# leg_module.net
KiCad netlist of a schematic drawn in Altium Designer
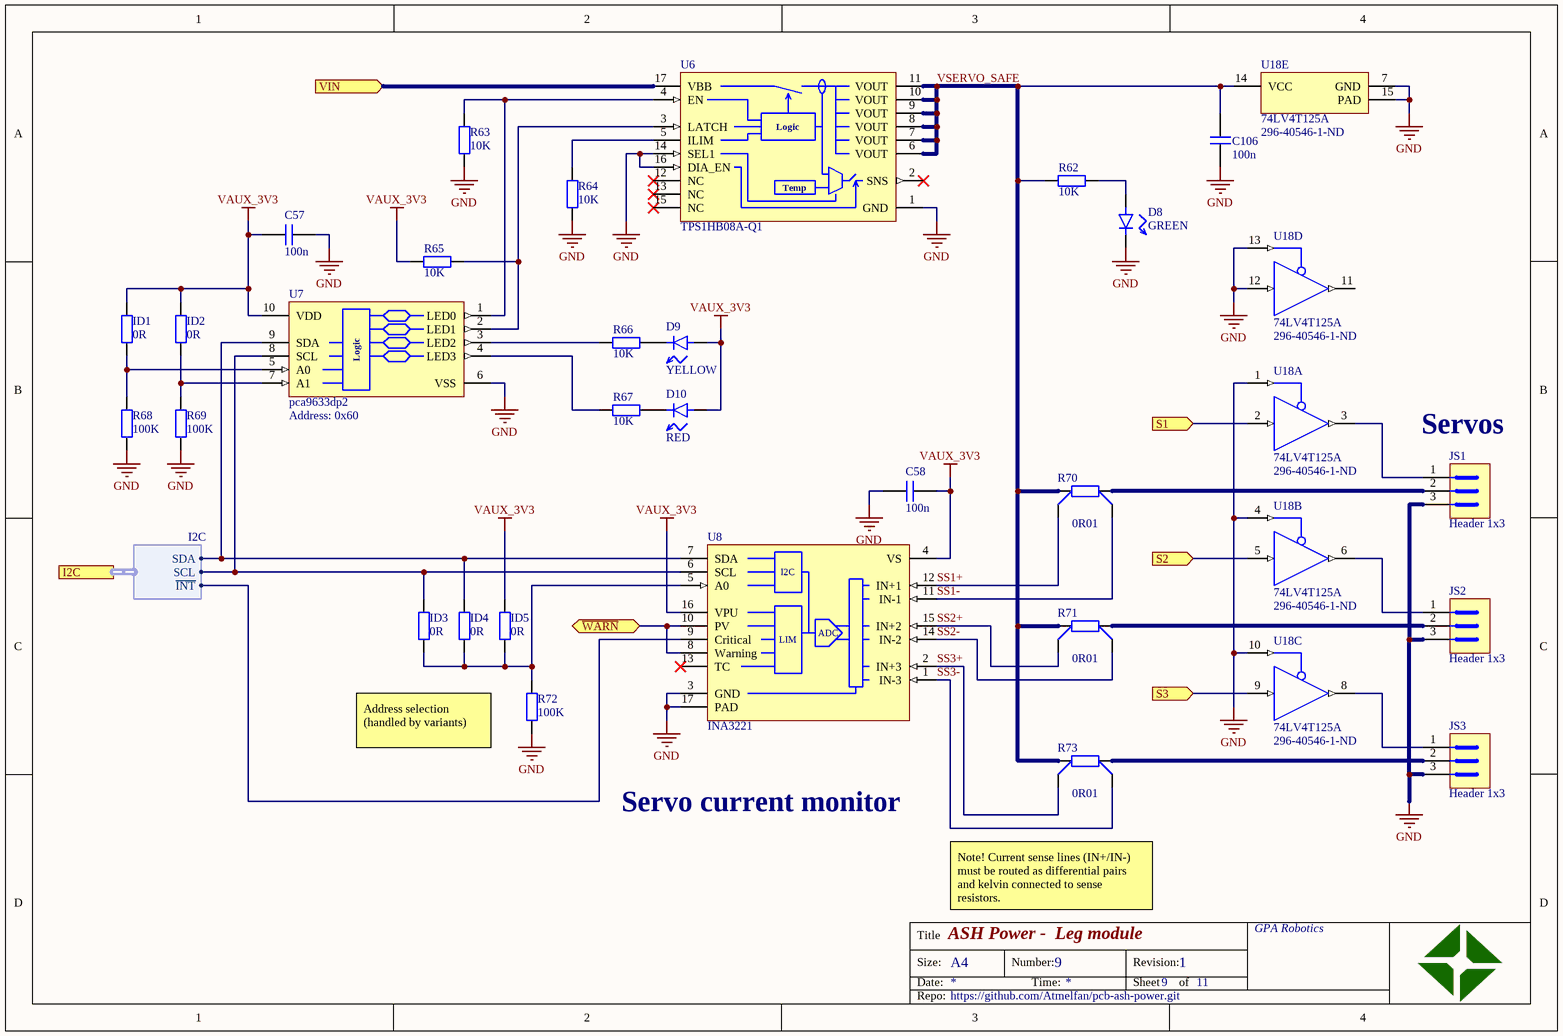
[diagram p0: leg_module.SchDoc]

(export (version "E")
  (design (tool "Eeschema 10.0.6"))
  (components
    (comp (ref "C57")
      (value "100n")
      (footprint "CAPC1005X06N")
      (description "Capacitor")
      (fields (field (name "Comment") "cap"))
      (libsource (lib "lib_passives") (part "cap"))
    )
    (comp (ref "C58")
      (value "100n")
      (footprint "CAPC1005X06N")
      (description "Capacitor")
      (fields (field (name "Comment") "cap"))
      (libsource (lib "lib_passives") (part "cap"))
    )
    (comp (ref "C106")
      (value "100n")
      (footprint "CAPC1005X06N")
      (description "Capacitor")
      (fields (field (name "Comment") "cap"))
      (libsource (lib "lib_passives") (part "cap"))
    )
    (comp (ref "D8")
      (value "GREEN")
      (footprint "CAPCP1005X06N")
      (description "LED")
      (fields (field (name "Comment") "led"))
      (libsource (lib "lib_actives") (part "led"))
    )
    (comp (ref "D9")
      (value "YELLOW")
      (footprint "CAPCP1005X06N")
      (description "LED")
      (fields (field (name "Comment") "led"))
      (libsource (lib "lib_actives") (part "led"))
    )
    (comp (ref "D10")
      (value "RED")
      (footprint "CAPCP1005X06N")
      (description "LED")
      (fields (field (name "Comment") "led"))
      (libsource (lib "lib_actives") (part "led"))
    )
    (comp (ref "ID1")
      (value "0R")
      (footprint "RESC1005X04N")
      (description "Resistor")
      (fields (field (name "Comment") "res"))
      (libsource (lib "") (part "res_1"))
    )
    (comp (ref "ID2")
      (value "0R")
      (footprint "RESC1005X04N")
      (description "Resistor")
      (fields (field (name "Comment") "res"))
      (libsource (lib "") (part "res_1"))
    )
    (comp (ref "ID3")
      (value "0R")
      (footprint "RESC1005X04N")
      (description "Resistor")
      (fields (field (name "Comment") "res"))
      (libsource (lib "") (part "res_1"))
    )
    (comp (ref "ID4")
      (value "0R")
      (footprint "RESC1005X04N")
      (description "Resistor")
      (fields (field (name "Comment") "res"))
      (libsource (lib "") (part "res_1"))
    )
    (comp (ref "ID5")
      (value "0R")
      (footprint "RESC1005X04N")
      (description "Resistor")
      (fields (field (name "Comment") "res"))
      (libsource (lib "") (part "res_1"))
    )
    (comp (ref "JS1")
      (value "Header 1x3")
      (footprint "HEADER_1x3_100MIL")
      (description "2.54mm pitch single row header")
      (libsource (lib "lib_connectors") (part "header_1x3_100mil"))
    )
    (comp (ref "JS2")
      (value "Header 1x3")
      (footprint "HEADER_1x3_100MIL")
      (description "2.54mm pitch single row header")
      (libsource (lib "lib_connectors") (part "header_1x3_100mil"))
    )
    (comp (ref "JS3")
      (value "Header 1x3")
      (footprint "HEADER_1x3_100MIL")
      (description "2.54mm pitch single row header")
      (libsource (lib "lib_connectors") (part "header_1x3_100mil"))
    )
    (comp (ref "R62")
      (value "10K")
      (footprint "RESC1005X04N")
      (description "Resistor")
      (fields (field (name "Comment") "res"))
      (libsource (lib "") (part "res_2"))
    )
    (comp (ref "R63")
      (value "10K")
      (footprint "RESC1005X04N")
      (description "Resistor")
      (fields (field (name "Comment") "res"))
      (libsource (lib "") (part "res_1"))
    )
    (comp (ref "R64")
      (value "10K")
      (footprint "RESC1005X04N")
      (description "Resistor")
      (fields (field (name "Comment") "res"))
      (libsource (lib "") (part "res_1"))
    )
    (comp (ref "R65")
      (value "10K")
      (footprint "RESC1005X04N")
      (description "Resistor")
      (fields (field (name "Comment") "res"))
      (libsource (lib "") (part "res_2"))
    )
    (comp (ref "R66")
      (value "10K")
      (footprint "RESC1005X04N")
      (description "Resistor")
      (fields (field (name "Comment") "res"))
      (libsource (lib "lib_passives") (part "res"))
    )
    (comp (ref "R67")
      (value "10K")
      (footprint "RESC1005X04N")
      (description "Resistor")
      (fields (field (name "Comment") "res"))
      (libsource (lib "lib_passives") (part "res"))
    )
    (comp (ref "R68")
      (value "100K")
      (footprint "RESC1005X04N")
      (description "Resistor")
      (fields (field (name "Comment") "res"))
      (libsource (lib "") (part "res_1"))
    )
    (comp (ref "R69")
      (value "100K")
      (footprint "RESC1005X04N")
      (description "Resistor")
      (fields (field (name "Comment") "res"))
      (libsource (lib "") (part "res_1"))
    )
    (comp (ref "R70")
      (value "0R01")
      (footprint "4T_RESC1632X05N")
      (description "Resistor")
      (fields (field (name "Comment") "res_4t"))
      (libsource (lib "lib_passives") (part "res_4t"))
    )
    (comp (ref "R71")
      (value "0R01")
      (footprint "4T_RESC1632X05N")
      (description "Resistor")
      (fields (field (name "Comment") "res_4t"))
      (libsource (lib "lib_passives") (part "res_4t"))
    )
    (comp (ref "R72")
      (value "100K")
      (footprint "RESC1005X04N")
      (description "Resistor")
      (fields (field (name "Comment") "res"))
      (libsource (lib "") (part "res_1"))
    )
    (comp (ref "R73")
      (value "0R01")
      (footprint "4T_RESC1632X05N")
      (description "Resistor")
      (fields (field (name "Comment") "res_4t"))
      (libsource (lib "lib_passives") (part "res_4t"))
    )
    (comp (ref "U6")
      (value "TPS1HB08A-Q1")
      (footprint "TSOP65P640X120_HS-17N_TPS1HB08")
      (description "40-V, 8-mΩ Single-Channel Smart High-Side Switch")
      (libsource (lib "lib_ti") (part "tps1hb08a"))
    )
    (comp (ref "U7")
      (value "pca9633dp2")
      (footprint "TSSOP50P490X110-10N_PCA9633DP2")
      (description "4-bit Fm+ I2C-bus LED driver")
      (fields (field (name "ADDRESS") "0x60"))
      (libsource (lib "lib_nxp") (part "pca9633dp2"))
    )
    (comp (ref "U8")
      (value "INA3221")
      (footprint "QFN65P400X400X100_HS-17N_INA3221")
      (libsource (lib "lib_ti") (part "ina3221"))
    )
    (comp (ref "U18")
      (value "74LV4T125A")
      (footprint "QFN50P350X350X100_HS-15N")
      (description "Quadruple Bus Buffer Gates With 3-State Outputs")
      (fields (field (name "SUPPLIER PART NUMBER 1") "296-40546-1-ND"))
      (libsource (lib "lib_ti") (part "sn74lv4t125a"))
    )
  )
  (nets
    (net (code "2") (name "/S1") (class "Default")
      (node (ref "U18") (pin "2") (pinfunction "1A_2") (pintype "input"))
    )
    (net (code "3") (name "/S2") (class "Default")
      (node (ref "U18") (pin "5") (pinfunction "2A_5") (pintype "input"))
    )
    (net (code "4") (name "/S3") (class "Default")
      (node (ref "U18") (pin "9") (pinfunction "3A_9") (pintype "input"))
    )
    (net (code "5") (name "/SCL") (class "Default")
      (node (ref "ID3") (pin "2") (pinfunction "2_2") (pintype "passive"))
      (node (ref "U7") (pin "8") (pinfunction "SCL_8") (pintype "open_collector"))
      (node (ref "U8") (pin "6") (pinfunction "SCL_6") (pintype "open_collector"))
    )
    (net (code "6") (name "/SDA") (class "Default")
      (node (ref "ID4") (pin "2") (pinfunction "2_2") (pintype "passive"))
      (node (ref "U7") (pin "9") (pinfunction "SDA_9") (pintype "open_collector"))
      (node (ref "U8") (pin "7") (pinfunction "SDA_7") (pintype "open_collector"))
    )
    (net (code "7") (name "/SS1+") (class "Default")
      (node (ref "R70") (pin "3") (pinfunction "3_3") (pintype "passive"))
      (node (ref "U8") (pin "12") (pinfunction "IN+1_12") (pintype "input"))
    )
    (net (code "8") (name "/SS1-") (class "Default")
      (node (ref "R70") (pin "4") (pinfunction "4_4") (pintype "passive"))
      (node (ref "U8") (pin "11") (pinfunction "IN-1_11") (pintype "input"))
    )
    (net (code "9") (name "/SS2+") (class "Default")
      (node (ref "R71") (pin "3") (pinfunction "3_3") (pintype "passive"))
      (node (ref "U8") (pin "15") (pinfunction "IN+2_15") (pintype "input"))
    )
    (net (code "10") (name "/SS2-") (class "Default")
      (node (ref "R71") (pin "4") (pinfunction "4_4") (pintype "passive"))
      (node (ref "U8") (pin "14") (pinfunction "IN-2_14") (pintype "input"))
    )
    (net (code "11") (name "/SS3+") (class "Default")
      (node (ref "R73") (pin "3") (pinfunction "3_3") (pintype "passive"))
      (node (ref "U8") (pin "2") (pinfunction "IN+3_2") (pintype "input"))
    )
    (net (code "12") (name "/SS3-") (class "Default")
      (node (ref "R73") (pin "4") (pinfunction "4_4") (pintype "passive"))
      (node (ref "U8") (pin "1") (pinfunction "IN-3_1") (pintype "input"))
    )
    (net (code "13") (name "/VIN") (class "Default")
      (node (ref "U6") (pin "17") (pinfunction "VBB_17") (pintype "power_in"))
    )
    (net (code "14") (name "/VSERVO_SAFE") (class "Default")
      (node (ref "C106") (pin "2") (pinfunction "2_2") (pintype "passive"))
      (node (ref "R62") (pin "1") (pinfunction "1_1") (pintype "passive"))
      (node (ref "R70") (pin "1") (pinfunction "1_1") (pintype "passive"))
      (node (ref "R71") (pin "1") (pinfunction "1_1") (pintype "passive"))
      (node (ref "R73") (pin "1") (pinfunction "1_1") (pintype "passive"))
      (node (ref "U18") (pin "14") (pinfunction "VCC_14") (pintype "power_in"))
      (node (ref "U6") (pin "10") (pinfunction "VOUT_10") (pintype "power_in"))
      (node (ref "U6") (pin "11") (pinfunction "VOUT_11") (pintype "power_in"))
      (node (ref "U6") (pin "6") (pinfunction "VOUT_6") (pintype "power_in"))
      (node (ref "U6") (pin "7") (pinfunction "VOUT_7") (pintype "power_in"))
      (node (ref "U6") (pin "8") (pinfunction "VOUT_8") (pintype "power_in"))
      (node (ref "U6") (pin "9") (pinfunction "VOUT_9") (pintype "power_in"))
    )
    (net (code "15") (name "/WARN") (class "Default")
      (node (ref "U8") (pin "10") (pinfunction "PV_10") (pintype "open_collector"))
      (node (ref "U8") (pin "8") (pinfunction "Warning_8") (pintype "open_collector"))
    )
    (net (code "17") (name "/~{INT}") (class "Default")
      (node (ref "U8") (pin "9") (pinfunction "Critical_9") (pintype "open_collector"))
    )
    (net (code "18") (name "GND") (class "Default")
      (node (ref "C106") (pin "1") (pinfunction "1_1") (pintype "passive"))
      (node (ref "C57") (pin "1") (pinfunction "1_1") (pintype "passive"))
      (node (ref "C58") (pin "1") (pinfunction "1_1") (pintype "passive"))
      (node (ref "D8") (pin "C") (pinfunction "C_C") (pintype "passive"))
      (node (ref "JS1") (pin "3") (pinfunction "3_3") (pintype "passive"))
      (node (ref "JS2") (pin "3") (pinfunction "3_3") (pintype "passive"))
      (node (ref "JS3") (pin "3") (pinfunction "3_3") (pintype "passive"))
      (node (ref "R63") (pin "1") (pinfunction "1_1") (pintype "passive"))
      (node (ref "R64") (pin "1") (pinfunction "1_1") (pintype "passive"))
      (node (ref "R68") (pin "1") (pinfunction "1_1") (pintype "passive"))
      (node (ref "R69") (pin "1") (pinfunction "1_1") (pintype "passive"))
      (node (ref "R72") (pin "1") (pinfunction "1_1") (pintype "passive"))
      (node (ref "U18") (pin "1") (pinfunction "1OE_1") (pintype "input"))
      (node (ref "U18") (pin "10") (pinfunction "3OE_10") (pintype "input"))
      (node (ref "U18") (pin "12") (pinfunction "4A_12") (pintype "input"))
      (node (ref "U18") (pin "13") (pinfunction "4OE_13") (pintype "input"))
      (node (ref "U18") (pin "15") (pinfunction "PAD_15") (pintype "passive"))
      (node (ref "U18") (pin "4") (pinfunction "2OE_4") (pintype "input"))
      (node (ref "U18") (pin "7") (pinfunction "GND_7") (pintype "power_in"))
      (node (ref "U6") (pin "1") (pinfunction "GND_1") (pintype "power_in"))
      (node (ref "U6") (pin "14") (pinfunction "SEL1_14") (pintype "input"))
      (node (ref "U6") (pin "16") (pinfunction "DIA_EN_16") (pintype "input"))
      (node (ref "U7") (pin "6") (pinfunction "VSS_6") (pintype "power_in"))
      (node (ref "U8") (pin "17") (pinfunction "PAD_17") (pintype "power_in"))
      (node (ref "U8") (pin "3") (pinfunction "GND_3") (pintype "power_in"))
    )
    (net (code "19") (name "Net-(D8-PadA)") (class "Default")
      (node (ref "D8") (pin "A") (pinfunction "A_A") (pintype "passive"))
      (node (ref "R62") (pin "2") (pinfunction "2_2") (pintype "passive"))
    )
    (net (code "20") (name "Net-(D9-PadC)") (class "Default")
      (node (ref "D9") (pin "C") (pinfunction "C_C") (pintype "passive"))
      (node (ref "R66") (pin "1") (pinfunction "1_1") (pintype "passive"))
    )
    (net (code "21") (name "Net-(D10-PadC)") (class "Default")
      (node (ref "D10") (pin "C") (pinfunction "C_C") (pintype "passive"))
      (node (ref "R67") (pin "1") (pinfunction "1_1") (pintype "passive"))
    )
    (net (code "22") (name "Net-(JS1-Pad2)") (class "Default")
      (node (ref "JS1") (pin "2") (pinfunction "2_2") (pintype "passive"))
      (node (ref "R70") (pin "2") (pinfunction "2_2") (pintype "passive"))
    )
    (net (code "23") (name "Net-(JS2-Pad2)") (class "Default")
      (node (ref "JS2") (pin "2") (pinfunction "2_2") (pintype "passive"))
      (node (ref "R71") (pin "2") (pinfunction "2_2") (pintype "passive"))
    )
    (net (code "24") (name "Net-(JS3-Pad2)") (class "Default")
      (node (ref "JS3") (pin "2") (pinfunction "2_2") (pintype "passive"))
      (node (ref "R73") (pin "2") (pinfunction "2_2") (pintype "passive"))
    )
    (net (code "25") (name "Net-(U6-EN)") (class "Default")
      (node (ref "R63") (pin "2") (pinfunction "2_2") (pintype "passive"))
      (node (ref "U6") (pin "4") (pinfunction "EN_4") (pintype "input"))
      (node (ref "U7") (pin "1") (pinfunction "LED0_1") (pintype "output"))
    )
    (net (code "26") (name "Net-(U6-ILIM)") (class "Default")
      (node (ref "R64") (pin "2") (pinfunction "2_2") (pintype "passive"))
      (node (ref "U6") (pin "5") (pinfunction "ILIM_5") (pintype "passive"))
    )
    (net (code "27") (name "Net-(U6-LATCH)") (class "Default")
      (node (ref "R65") (pin "2") (pinfunction "2_2") (pintype "passive"))
      (node (ref "U6") (pin "3") (pinfunction "LATCH_3") (pintype "input"))
      (node (ref "U7") (pin "2") (pinfunction "LED1_2") (pintype "output"))
    )
    (net (code "28") (name "Net-(U7-A0)") (class "Default")
      (node (ref "ID1") (pin "1") (pinfunction "1_1") (pintype "passive"))
      (node (ref "R68") (pin "2") (pinfunction "2_2") (pintype "passive"))
      (node (ref "U7") (pin "5") (pinfunction "A0_5") (pintype "input"))
    )
    (net (code "29") (name "Net-(U7-A1)") (class "Default")
      (node (ref "ID2") (pin "1") (pinfunction "1_1") (pintype "passive"))
      (node (ref "R69") (pin "2") (pinfunction "2_2") (pintype "passive"))
      (node (ref "U7") (pin "7") (pinfunction "A1_7") (pintype "input"))
    )
    (net (code "30") (name "Net-(U7-LED2)") (class "Default")
      (node (ref "R66") (pin "2") (pinfunction "2_2") (pintype "passive"))
      (node (ref "U7") (pin "3") (pinfunction "LED2_3") (pintype "output"))
    )
    (net (code "31") (name "Net-(U7-LED3)") (class "Default")
      (node (ref "R67") (pin "2") (pinfunction "2_2") (pintype "passive"))
      (node (ref "U7") (pin "4") (pinfunction "LED3_4") (pintype "output"))
    )
    (net (code "32") (name "Net-(U8-A0)") (class "Default")
      (node (ref "ID3") (pin "1") (pinfunction "1_1") (pintype "passive"))
      (node (ref "ID4") (pin "1") (pinfunction "1_1") (pintype "passive"))
      (node (ref "ID5") (pin "1") (pinfunction "1_1") (pintype "passive"))
      (node (ref "R72") (pin "2") (pinfunction "2_2") (pintype "passive"))
      (node (ref "U8") (pin "5") (pinfunction "A0_5") (pintype "input"))
    )
    (net (code "33") (name "Net-(U18A-1Y)") (class "Default")
      (node (ref "JS1") (pin "1") (pinfunction "1_1") (pintype "passive"))
      (node (ref "U18") (pin "3") (pinfunction "1Y_3") (pintype "output"))
    )
    (net (code "34") (name "Net-(U18B-2Y)") (class "Default")
      (node (ref "JS2") (pin "1") (pinfunction "1_1") (pintype "passive"))
      (node (ref "U18") (pin "6") (pinfunction "2Y_6") (pintype "output"))
    )
    (net (code "35") (name "Net-(U18C-3Y)") (class "Default")
      (node (ref "JS3") (pin "1") (pinfunction "1_1") (pintype "passive"))
      (node (ref "U18") (pin "8") (pinfunction "3Y_8") (pintype "output"))
    )
    (net (code "36") (name "VAUX_3V3") (class "Default")
      (node (ref "C57") (pin "2") (pinfunction "2_2") (pintype "passive"))
      (node (ref "C58") (pin "2") (pinfunction "2_2") (pintype "passive"))
      (node (ref "D10") (pin "A") (pinfunction "A_A") (pintype "passive"))
      (node (ref "D9") (pin "A") (pinfunction "A_A") (pintype "passive"))
      (node (ref "ID1") (pin "2") (pinfunction "2_2") (pintype "passive"))
      (node (ref "ID2") (pin "2") (pinfunction "2_2") (pintype "passive"))
      (node (ref "ID5") (pin "2") (pinfunction "2_2") (pintype "passive"))
      (node (ref "R65") (pin "1") (pinfunction "1_1") (pintype "passive"))
      (node (ref "U7") (pin "10") (pinfunction "VDD_10") (pintype "power_in"))
      (node (ref "U8") (pin "16") (pinfunction "VPU_16") (pintype "power_in"))
      (node (ref "U8") (pin "4") (pinfunction "VS_4") (pintype "power_in"))
    )
    (net (code "37") (name "unconnected-(U6-NC-Pad12)") (class "Default")
      (node (ref "U6") (pin "12") (pinfunction "NC_12") (pintype "passive+no_connect"))
    )
    (net (code "38") (name "unconnected-(U6-NC-Pad13)") (class "Default")
      (node (ref "U6") (pin "13") (pinfunction "NC_13") (pintype "passive+no_connect"))
    )
    (net (code "39") (name "unconnected-(U6-NC-Pad15)") (class "Default")
      (node (ref "U6") (pin "15") (pinfunction "NC_15") (pintype "passive+no_connect"))
    )
    (net (code "40") (name "unconnected-(U6-SNS-Pad2)") (class "Default")
      (node (ref "U6") (pin "2") (pinfunction "SNS_2") (pintype "output+no_connect"))
    )
    (net (code "41") (name "unconnected-(U8-TC-Pad13)") (class "Default")
      (node (ref "U8") (pin "13") (pinfunction "TC_13") (pintype "open_collector+no_connect"))
    )
    (net (code "42") (name "unconnected-(U18D-4Y-Pad11)") (class "Default")
      (node (ref "U18") (pin "11") (pinfunction "4Y_11") (pintype "output"))
    )
  )
)
